# Kajtu_-DSP_block_diagram.net
KiCad netlist of a schematic drawn in Altium Designer
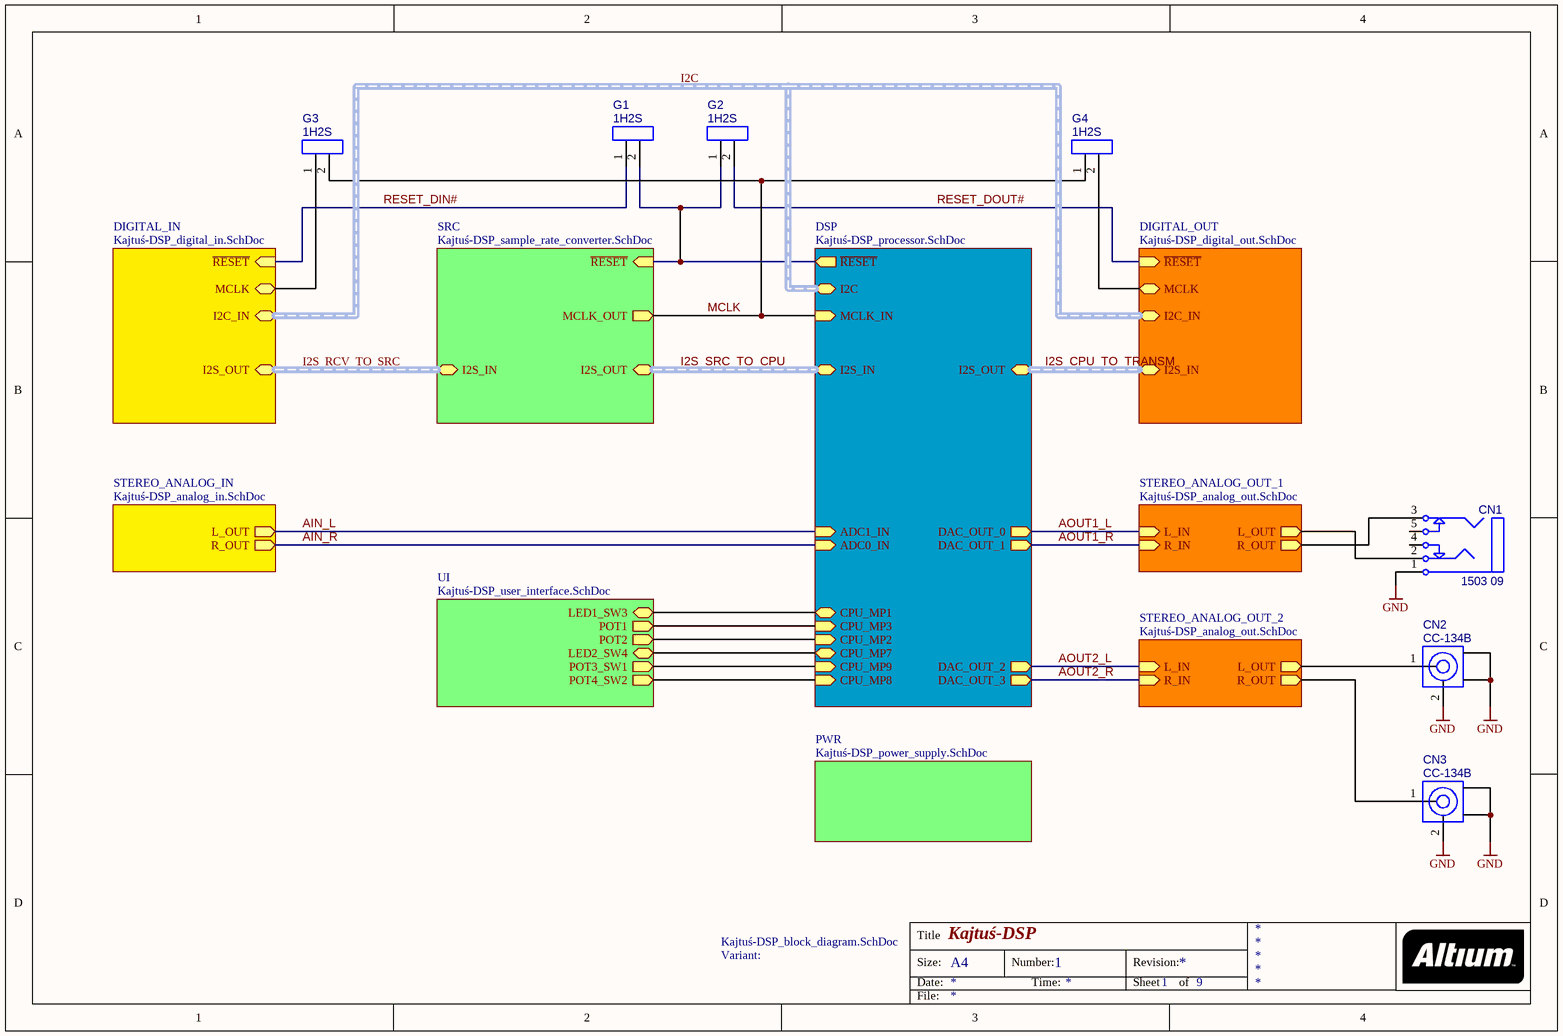
[diagram p0: Kajtuś-DSP_block_diagram.SchDoc]

(export (version "E")
  (design (tool "Eeschema 10.0.6"))
  (components
    (comp (ref "CN1")
      (value "1503 09")
      (footprint "CN_JACK_3.5_STEREO_1503-09")
      (description "3-Conductor Jack with 2 break contacts (normals) and 2 auxiliary make contacts")
      (fields (field (name "MANUFACTURER") "Lumberg"))
      (libsource (lib "AD_ostry_intlib") (part "CN_JACK_3.5_STEREO_1503-09"))
    )
    (comp (ref "CN2")
      (value "CC-134B")
      (footprint "CN_RCA_CC-134x")
      (description "Gniazdo RCA, żeńskie, ekranowane, kątowe 90°; do druku, THT, niklowane")
      (fields (field (name "PART NUMBER") "CN_RCA_CC-134B") (field (name "MANUFACTURER") "??"))
      (libsource (lib "AD_ostry_intlib") (part "CN_RCA_CC-134B"))
    )
    (comp (ref "CN3")
      (value "CC-134B")
      (footprint "CN_RCA_CC-134x")
      (description "Gniazdo RCA, żeńskie, ekranowane, kątowe 90°; do druku, THT, niklowane")
      (fields (field (name "PART NUMBER") "CN_RCA_CC-134B") (field (name "MANUFACTURER") "??"))
      (libsource (lib "AD_ostry_intlib") (part "CN_RCA_CC-134B"))
    )
    (comp (ref "G1")
      (value "1H2S")
      (footprint "1H2S_FHS")
      (description "Listwa jednorzędowa, 1x2 piny, raster 2,54mm")
      (fields (field (name "PART NUMBER") "G_1H2S") (field (name "MANUFACTURER") "generic"))
      (libsource (lib "AD_ostry_intlib") (part "G_1H2S"))
    )
    (comp (ref "G2")
      (value "1H2S")
      (footprint "1H2S_FHS")
      (description "Listwa jednorzędowa, 1x2 piny, raster 2,54mm")
      (fields (field (name "PART NUMBER") "G_1H2S") (field (name "MANUFACTURER") "generic"))
      (libsource (lib "AD_ostry_intlib") (part "G_1H2S"))
    )
    (comp (ref "G3")
      (value "1H2S")
      (footprint "1H2S_FHS")
      (description "Listwa jednorzędowa, 1x2 piny, raster 2,54mm")
      (fields (field (name "PART NUMBER") "G_1H2S") (field (name "MANUFACTURER") "generic"))
      (libsource (lib "AD_ostry_intlib") (part "G_1H2S"))
    )
    (comp (ref "G4")
      (value "1H2S")
      (footprint "1H2S_FHS")
      (description "Listwa jednorzędowa, 1x2 piny, raster 2,54mm")
      (fields (field (name "PART NUMBER") "G_1H2S") (field (name "MANUFACTURER") "generic"))
      (libsource (lib "AD_ostry_intlib") (part "G_1H2S"))
    )
  )
  (nets
    (net (code "13") (name "/L_OUT") (class "Default")
      (node (ref "CN2") (pin "1") (pinfunction "1_1") (pintype "passive"))
    )
    (net (code "14") (name "/L_OUT_1") (class "Default")
      (node (ref "CN1") (pin "2") (pinfunction "2_2") (pintype "passive"))
    )
    (net (code "15") (name "/MCLK") (class "Default")
      (node (ref "G3") (pin "2") (pinfunction "2_2") (pintype "passive"))
      (node (ref "G4") (pin "1") (pinfunction "1_1") (pintype "passive"))
    )
    (net (code "16") (name "/MCLK_1") (class "Default")
      (node (ref "G3") (pin "1") (pinfunction "1_1") (pintype "passive"))
    )
    (net (code "17") (name "/MCLK_2") (class "Default")
      (node (ref "G4") (pin "2") (pinfunction "2_2") (pintype "passive"))
    )
    (net (code "22") (name "/RESET_DIN#") (class "Default")
      (node (ref "G1") (pin "1") (pinfunction "1_1") (pintype "passive"))
    )
    (net (code "23") (name "/RESET_DOUT#") (class "Default")
      (node (ref "G2") (pin "2") (pinfunction "2_2") (pintype "passive"))
    )
    (net (code "24") (name "/R_OUT") (class "Default")
      (node (ref "CN3") (pin "1") (pinfunction "1_1") (pintype "passive"))
    )
    (net (code "25") (name "/R_OUT_1") (class "Default")
      (node (ref "CN1") (pin "3") (pinfunction "3_3") (pintype "passive"))
    )
    (net (code "30") (name "/~{RESET}") (class "Default")
      (node (ref "G1") (pin "2") (pinfunction "2_2") (pintype "passive"))
      (node (ref "G2") (pin "1") (pinfunction "1_1") (pintype "passive"))
    )
    (net (code "31") (name "GND") (class "Default")
      (node (ref "CN1") (pin "1") (pinfunction "1_1") (pintype "passive"))
      (node (ref "CN2") (pin "2") (pinfunction "2_2") (pintype "passive"))
      (node (ref "CN2") (pin "SH1") (pinfunction "SH1_SH1") (pintype "passive"))
      (node (ref "CN2") (pin "SH2") (pinfunction "SH2_SH2") (pintype "passive"))
      (node (ref "CN3") (pin "2") (pinfunction "2_2") (pintype "passive"))
      (node (ref "CN3") (pin "SH1") (pinfunction "SH1_SH1") (pintype "passive"))
      (node (ref "CN3") (pin "SH2") (pinfunction "SH2_SH2") (pintype "passive"))
    )
    (net (code "32") (name "unconnected-(CN1-Pad4)") (class "Default")
      (node (ref "CN1") (pin "4") (pinfunction "4_4") (pintype "passive"))
    )
    (net (code "33") (name "unconnected-(CN1-Pad5)") (class "Default")
      (node (ref "CN1") (pin "5") (pinfunction "5_5") (pintype "passive"))
    )
  )
)
